# VALVEBOARD_DigitalPower.net
KiCad netlist of a schematic drawn in Altium Designer
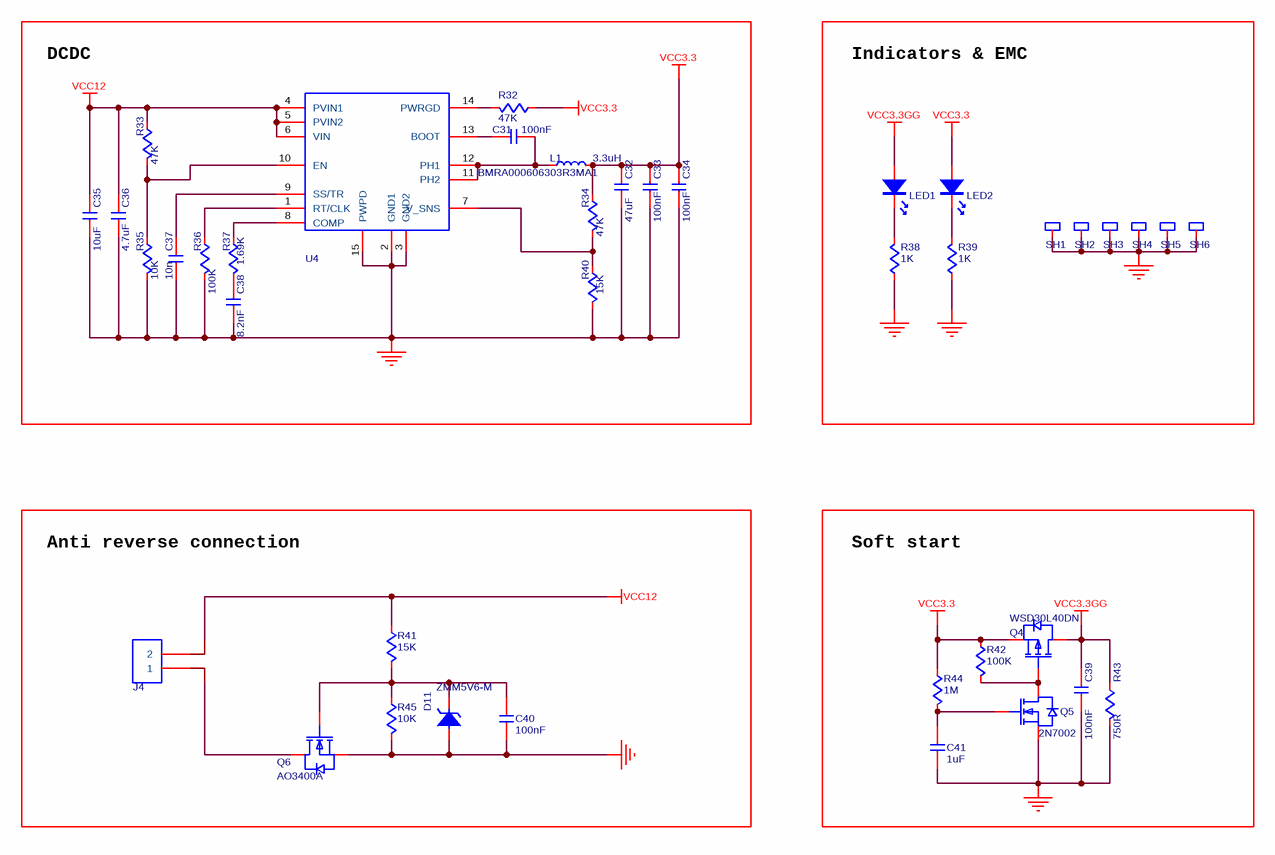
[diagram p0: VALVEBOARD_DigitalPower.SchDoc]

(export (version "E")
  (design (tool "Eeschema 10.0.6"))
  (components
    (comp (ref "C31")
      (value "100nF")
      (footprint "zynq:C0402")
      (fields (field (name "VOLTAGE") "25V") (field (name "Comment") "C-NOMO"))
      (libsource (lib "zynq") (part "C-NOMO"))
    )
    (comp (ref "C32")
      (value "47uF")
      (footprint "zynq:C0805")
      (fields (field (name "VOLTAGE") "25V") (field (name "Comment") "C-NOMO"))
      (libsource (lib "zynq") (part "C-NOMO"))
    )
    (comp (ref "C33")
      (value "100nF")
      (footprint "zynq:C0402")
      (fields (field (name "VOLTAGE") "25V") (field (name "Comment") "C-NOMO"))
      (libsource (lib "zynq") (part "C-NOMO"))
    )
    (comp (ref "C34")
      (value "100nF")
      (footprint "zynq:C0402")
      (fields (field (name "VOLTAGE") "25V") (field (name "Comment") "C-NOMO"))
      (libsource (lib "zynq") (part "C-NOMO"))
    )
    (comp (ref "C35")
      (value "10uF")
      (footprint "zynq:C0805")
      (fields (field (name "VOLTAGE") "25V") (field (name "Comment") "C-NOMO"))
      (libsource (lib "zynq") (part "C-NOMO"))
    )
    (comp (ref "C36")
      (value "4.7uF")
      (footprint "zynq:C0805")
      (fields (field (name "VOLTAGE") "25V") (field (name "Comment") "C-NOMO"))
      (libsource (lib "zynq") (part "C-NOMO"))
    )
    (comp (ref "C37")
      (value "10n")
      (footprint "zynq:C0402")
      (fields (field (name "VOLTAGE") "25V") (field (name "Comment") "C-NOMO"))
      (libsource (lib "zynq") (part "C-NOMO"))
    )
    (comp (ref "C38")
      (value "8.2nF")
      (footprint "zynq:C0402")
      (fields (field (name "VOLTAGE") "25V") (field (name "Comment") "C-NOMO"))
      (libsource (lib "zynq") (part "C-NOMO"))
    )
    (comp (ref "C39")
      (value "100nF")
      (footprint "zynq:C0402")
      (fields (field (name "VOLTAGE") "25V") (field (name "Comment") "C-NOMO"))
      (libsource (lib "zynq") (part "C-NOMO"))
    )
    (comp (ref "C40")
      (value "100nF")
      (footprint "zynq:C0402")
      (fields (field (name "VOLTAGE") "25V") (field (name "Comment") "C-NOMO"))
      (libsource (lib "zynq") (part "C-NOMO"))
    )
    (comp (ref "C41")
      (value "1uF")
      (footprint "zynq:C0603")
      (fields (field (name "VOLTAGE") "25V") (field (name "Comment") "C-NOMO"))
      (libsource (lib "zynq") (part "C-NOMO"))
    )
    (comp (ref "D11") (value "ZMM5V6-M") (footprint "ZMM5V6-M") (libsource (lib "zynq") (part "ZMM5V6-M")))
    (comp (ref "J4")
      (value "HDR1X2")
      (footprint "zynq:KF301-5.0-2P")
      (libsource (lib "zynq") (part "HDR1X2"))
    )
    (comp (ref "L1")
      (value "BMRA000606303R3MA1")
      (footprint "zynq:FXL0624")
      (fields (field (name "ALTIUM_VALUE") "3.3uH") (field (name "PUBLISHER") "Altium Limited"))
      (libsource (lib "zynq") (part "L"))
    )
    (comp (ref "LED1") (value "LED") (footprint "zynq:LED0603") (libsource (lib "zynq") (part "LED")))
    (comp (ref "LED2") (value "LED") (footprint "zynq:LED0603") (libsource (lib "zynq") (part "LED")))
    (comp (ref "Q4")
      (value "WSD30L40DN")
      (footprint "WSD30L40DN")
      (libsource (lib "zynq") (part "WSD30L40DN"))
    )
    (comp (ref "Q5") (value "2N7002") (footprint "2N7002") (libsource (lib "zynq") (part "2N7002")))
    (comp (ref "Q6") (value "AO3400A") (footprint "AO3400A") (libsource (lib "zynq") (part "AO3400A")))
    (comp (ref "R32")
      (value "47K")
      (footprint "zynq:R0402")
      (fields (field (name "Comment") "R"))
      (libsource (lib "zynq") (part "R"))
    )
    (comp (ref "R33")
      (value "47K")
      (footprint "zynq:R0402")
      (fields (field (name "Comment") "R"))
      (libsource (lib "zynq") (part "R"))
    )
    (comp (ref "R34")
      (value "47K")
      (footprint "zynq:R0402")
      (fields (field (name "Comment") "R"))
      (libsource (lib "zynq") (part "R"))
    )
    (comp (ref "R35")
      (value "10K")
      (footprint "zynq:R0402")
      (fields (field (name "Comment") "R"))
      (libsource (lib "zynq") (part "R"))
    )
    (comp (ref "R36")
      (value "100K")
      (footprint "zynq:R0402")
      (fields (field (name "Comment") "R"))
      (libsource (lib "zynq") (part "R"))
    )
    (comp (ref "R37")
      (value "1.69K")
      (footprint "zynq:R0402")
      (fields (field (name "Comment") "R"))
      (libsource (lib "zynq") (part "R"))
    )
    (comp (ref "R38")
      (value "1K")
      (footprint "zynq:R0402")
      (fields (field (name "Comment") "R"))
      (libsource (lib "zynq") (part "R"))
    )
    (comp (ref "R39")
      (value "1K")
      (footprint "zynq:R0402")
      (fields (field (name "Comment") "R"))
      (libsource (lib "zynq") (part "R"))
    )
    (comp (ref "R40")
      (value "15K")
      (footprint "zynq:R0402")
      (fields (field (name "Comment") "R"))
      (libsource (lib "zynq") (part "R"))
    )
    (comp (ref "R41")
      (value "15K")
      (footprint "zynq:R0402")
      (fields (field (name "Comment") "R"))
      (libsource (lib "zynq") (part "R"))
    )
    (comp (ref "R42")
      (value "100K")
      (footprint "zynq:R0402")
      (fields (field (name "Comment") "R"))
      (libsource (lib "zynq") (part "R"))
    )
    (comp (ref "R43")
      (value "750R")
      (footprint "zynq:R0805")
      (fields (field (name "Comment") "R"))
      (libsource (lib "zynq") (part "R"))
    )
    (comp (ref "R44")
      (value "1M")
      (footprint "zynq:R0402")
      (fields (field (name "Comment") "R"))
      (libsource (lib "zynq") (part "R"))
    )
    (comp (ref "R45")
      (value "10K")
      (footprint "zynq:R0402")
      (fields (field (name "Comment") "R"))
      (libsource (lib "zynq") (part "R"))
    )
    (comp (ref "SH1")
      (value "SHIELDSUPPORT")
      (footprint "SHIELDSUPPORT1")
      (libsource (lib "zynq") (part "SHIELDSUPPORT"))
    )
    (comp (ref "SH2")
      (value "SHIELDSUPPORT")
      (footprint "SHIELDSUPPORT1")
      (libsource (lib "zynq") (part "SHIELDSUPPORT"))
    )
    (comp (ref "SH3")
      (value "SHIELDSUPPORT")
      (footprint "SHIELDSUPPORT1")
      (libsource (lib "zynq") (part "SHIELDSUPPORT"))
    )
    (comp (ref "SH4")
      (value "SHIELDSUPPORT")
      (footprint "SHIELDSUPPORT1")
      (libsource (lib "zynq") (part "SHIELDSUPPORT"))
    )
    (comp (ref "SH5")
      (value "SHIELDSUPPORT")
      (footprint "SHIELDSUPPORT1")
      (libsource (lib "zynq") (part "SHIELDSUPPORT"))
    )
    (comp (ref "SH6")
      (value "SHIELDSUPPORT")
      (footprint "SHIELDSUPPORT1")
      (libsource (lib "zynq") (part "SHIELDSUPPORT"))
    )
    (comp (ref "U4")
      (value "TPS54620")
      (footprint "zynq:TPS54620")
      (libsource (lib "zynq") (part "TPS54620"))
    )
  )
  (nets
    (net (code "1") (name "DGND") (class "Default")
      (node (ref "C32") (pin "1") (pinfunction "1_1") (pintype "passive"))
      (node (ref "C33") (pin "1") (pinfunction "1_1") (pintype "passive"))
      (node (ref "C34") (pin "1") (pinfunction "1_1") (pintype "passive"))
      (node (ref "C35") (pin "1") (pinfunction "1_1") (pintype "passive"))
      (node (ref "C36") (pin "1") (pinfunction "1_1") (pintype "passive"))
      (node (ref "C37") (pin "1") (pinfunction "1_1") (pintype "passive"))
      (node (ref "C38") (pin "1") (pinfunction "1_1") (pintype "passive"))
      (node (ref "C39") (pin "1") (pinfunction "1_1") (pintype "passive"))
      (node (ref "C40") (pin "1") (pinfunction "1_1") (pintype "passive"))
      (node (ref "C41") (pin "1") (pinfunction "1_1") (pintype "passive"))
      (node (ref "D11") (pin "2") (pinfunction "2_2") (pintype "passive"))
      (node (ref "Q5") (pin "S") (pinfunction "S_S") (pintype "passive"))
      (node (ref "Q6") (pin "S") (pinfunction "S_S") (pintype "passive"))
      (node (ref "R35") (pin "1") (pinfunction "1_1") (pintype "passive"))
      (node (ref "R36") (pin "1") (pinfunction "1_1") (pintype "passive"))
      (node (ref "R38") (pin "2") (pinfunction "2_2") (pintype "passive"))
      (node (ref "R39") (pin "2") (pinfunction "2_2") (pintype "passive"))
      (node (ref "R40") (pin "1") (pinfunction "1_1") (pintype "passive"))
      (node (ref "R43") (pin "1") (pinfunction "1_1") (pintype "passive"))
      (node (ref "R45") (pin "1") (pinfunction "1_1") (pintype "passive"))
      (node (ref "SH1") (pin "SH") (pinfunction "SH_SH") (pintype "passive"))
      (node (ref "SH2") (pin "SH") (pinfunction "SH_SH") (pintype "passive"))
      (node (ref "SH3") (pin "SH") (pinfunction "SH_SH") (pintype "passive"))
      (node (ref "SH4") (pin "SH") (pinfunction "SH_SH") (pintype "passive"))
      (node (ref "SH5") (pin "SH") (pinfunction "SH_SH") (pintype "passive"))
      (node (ref "SH6") (pin "SH") (pinfunction "SH_SH") (pintype "passive"))
      (node (ref "U4") (pin "15") (pinfunction "PWPD_15") (pintype "passive"))
      (node (ref "U4") (pin "2") (pinfunction "GND1_2") (pintype "passive"))
      (node (ref "U4") (pin "3") (pinfunction "GND2_3") (pintype "passive"))
    )
    (net (code "2") (name "Net-(C38-Pad2)") (class "Default")
      (node (ref "C38") (pin "2") (pinfunction "2_2") (pintype "passive"))
      (node (ref "R37") (pin "1") (pinfunction "1_1") (pintype "passive"))
    )
    (net (code "3") (name "Net-(C40-Pad2)") (class "Default")
      (node (ref "C40") (pin "2") (pinfunction "2_2") (pintype "passive"))
      (node (ref "D11") (pin "1") (pinfunction "1_1") (pintype "passive"))
      (node (ref "Q6") (pin "G") (pinfunction "G_G") (pintype "passive"))
      (node (ref "R41") (pin "1") (pinfunction "1_1") (pintype "passive"))
      (node (ref "R45") (pin "2") (pinfunction "2_2") (pintype "passive"))
    )
    (net (code "4") (name "Net-(C41-Pad2)") (class "Default")
      (node (ref "C41") (pin "2") (pinfunction "2_2") (pintype "passive"))
      (node (ref "Q5") (pin "G") (pinfunction "G_G") (pintype "passive"))
      (node (ref "R44") (pin "1") (pinfunction "1_1") (pintype "passive"))
    )
    (net (code "5") (name "Net-(J4-Pad1)") (class "Default")
      (node (ref "J4") (pin "1") (pinfunction "1_1") (pintype "passive"))
      (node (ref "Q6") (pin "D") (pinfunction "D_D") (pintype "passive"))
    )
    (net (code "6") (name "Net-(LED1-Pad1)") (class "Default")
      (node (ref "LED1") (pin "1") (pinfunction "1_1") (pintype "passive"))
      (node (ref "R38") (pin "1") (pinfunction "1_1") (pintype "passive"))
    )
    (net (code "7") (name "Net-(LED2-Pad1)") (class "Default")
      (node (ref "LED2") (pin "1") (pinfunction "1_1") (pintype "passive"))
      (node (ref "R39") (pin "1") (pinfunction "1_1") (pintype "passive"))
    )
    (net (code "8") (name "Net-(Q4-PadG)") (class "Default")
      (node (ref "Q4") (pin "G") (pinfunction "G_G") (pintype "passive"))
      (node (ref "Q5") (pin "D") (pinfunction "D_D") (pintype "passive"))
      (node (ref "R42") (pin "1") (pinfunction "1_1") (pintype "passive"))
    )
    (net (code "9") (name "Net-(U4-BOOT)") (class "Default")
      (node (ref "C31") (pin "1") (pinfunction "1_1") (pintype "passive"))
      (node (ref "U4") (pin "13") (pinfunction "BOOT_13") (pintype "passive"))
    )
    (net (code "10") (name "Net-(U4-COMP)") (class "Default")
      (node (ref "R37") (pin "2") (pinfunction "2_2") (pintype "passive"))
      (node (ref "U4") (pin "8") (pinfunction "COMP_8") (pintype "passive"))
    )
    (net (code "11") (name "Net-(U4-EN)") (class "Default")
      (node (ref "R33") (pin "1") (pinfunction "1_1") (pintype "passive"))
      (node (ref "R35") (pin "2") (pinfunction "2_2") (pintype "passive"))
      (node (ref "U4") (pin "10") (pinfunction "EN_10") (pintype "passive"))
    )
    (net (code "12") (name "Net-(U4-PH1)") (class "Default")
      (node (ref "C31") (pin "2") (pinfunction "2_2") (pintype "passive"))
      (node (ref "L1") (pin "1") (pinfunction "1_1") (pintype "passive"))
      (node (ref "U4") (pin "11") (pinfunction "PH2_11") (pintype "passive"))
      (node (ref "U4") (pin "12") (pinfunction "PH1_12") (pintype "passive"))
    )
    (net (code "13") (name "Net-(U4-PWRGD)") (class "Default")
      (node (ref "R32") (pin "1") (pinfunction "1_1") (pintype "passive"))
      (node (ref "U4") (pin "14") (pinfunction "PWRGD_14") (pintype "passive"))
    )
    (net (code "14") (name "Net-(U4-RT{slash}CLK)") (class "Default")
      (node (ref "R36") (pin "2") (pinfunction "2_2") (pintype "passive"))
      (node (ref "U4") (pin "1") (pinfunction "RT/CLK_1") (pintype "passive"))
    )
    (net (code "15") (name "Net-(U4-SS{slash}TR)") (class "Default")
      (node (ref "C37") (pin "2") (pinfunction "2_2") (pintype "passive"))
      (node (ref "U4") (pin "9") (pinfunction "SS/TR_9") (pintype "passive"))
    )
    (net (code "16") (name "Net-(U4-V_SNS)") (class "Default")
      (node (ref "R34") (pin "1") (pinfunction "1_1") (pintype "passive"))
      (node (ref "R40") (pin "2") (pinfunction "2_2") (pintype "passive"))
      (node (ref "U4") (pin "7") (pinfunction "V_SNS_7") (pintype "passive"))
    )
    (net (code "17") (name "VCC3.3") (class "Default")
      (node (ref "C32") (pin "2") (pinfunction "2_2") (pintype "passive"))
      (node (ref "C33") (pin "2") (pinfunction "2_2") (pintype "passive"))
      (node (ref "C34") (pin "2") (pinfunction "2_2") (pintype "passive"))
      (node (ref "L1") (pin "2") (pinfunction "2_2") (pintype "passive"))
      (node (ref "LED2") (pin "2") (pinfunction "2_2") (pintype "passive"))
      (node (ref "Q4") (pin "S") (pinfunction "S_S") (pintype "passive"))
      (node (ref "R32") (pin "2") (pinfunction "2_2") (pintype "passive"))
      (node (ref "R34") (pin "2") (pinfunction "2_2") (pintype "passive"))
      (node (ref "R42") (pin "2") (pinfunction "2_2") (pintype "passive"))
      (node (ref "R44") (pin "2") (pinfunction "2_2") (pintype "passive"))
    )
    (net (code "18") (name "VCC3.3GG") (class "Default")
      (node (ref "C39") (pin "2") (pinfunction "2_2") (pintype "passive"))
      (node (ref "LED1") (pin "2") (pinfunction "2_2") (pintype "passive"))
      (node (ref "Q4") (pin "D") (pinfunction "D_D") (pintype "passive"))
      (node (ref "R43") (pin "2") (pinfunction "2_2") (pintype "passive"))
    )
    (net (code "19") (name "VCC12") (class "Default")
      (node (ref "C35") (pin "2") (pinfunction "2_2") (pintype "passive"))
      (node (ref "C36") (pin "2") (pinfunction "2_2") (pintype "passive"))
      (node (ref "J4") (pin "2") (pinfunction "2_2") (pintype "passive"))
      (node (ref "R33") (pin "2") (pinfunction "2_2") (pintype "passive"))
      (node (ref "R41") (pin "2") (pinfunction "2_2") (pintype "passive"))
      (node (ref "U4") (pin "4") (pinfunction "PVIN1_4") (pintype "passive"))
      (node (ref "U4") (pin "5") (pinfunction "PVIN2_5") (pintype "passive"))
      (node (ref "U4") (pin "6") (pinfunction "VIN_6") (pintype "passive"))
    )
  )
)
